# CMUcam_Bridge.net
KiCad netlist of a schematic drawn in EAGLE
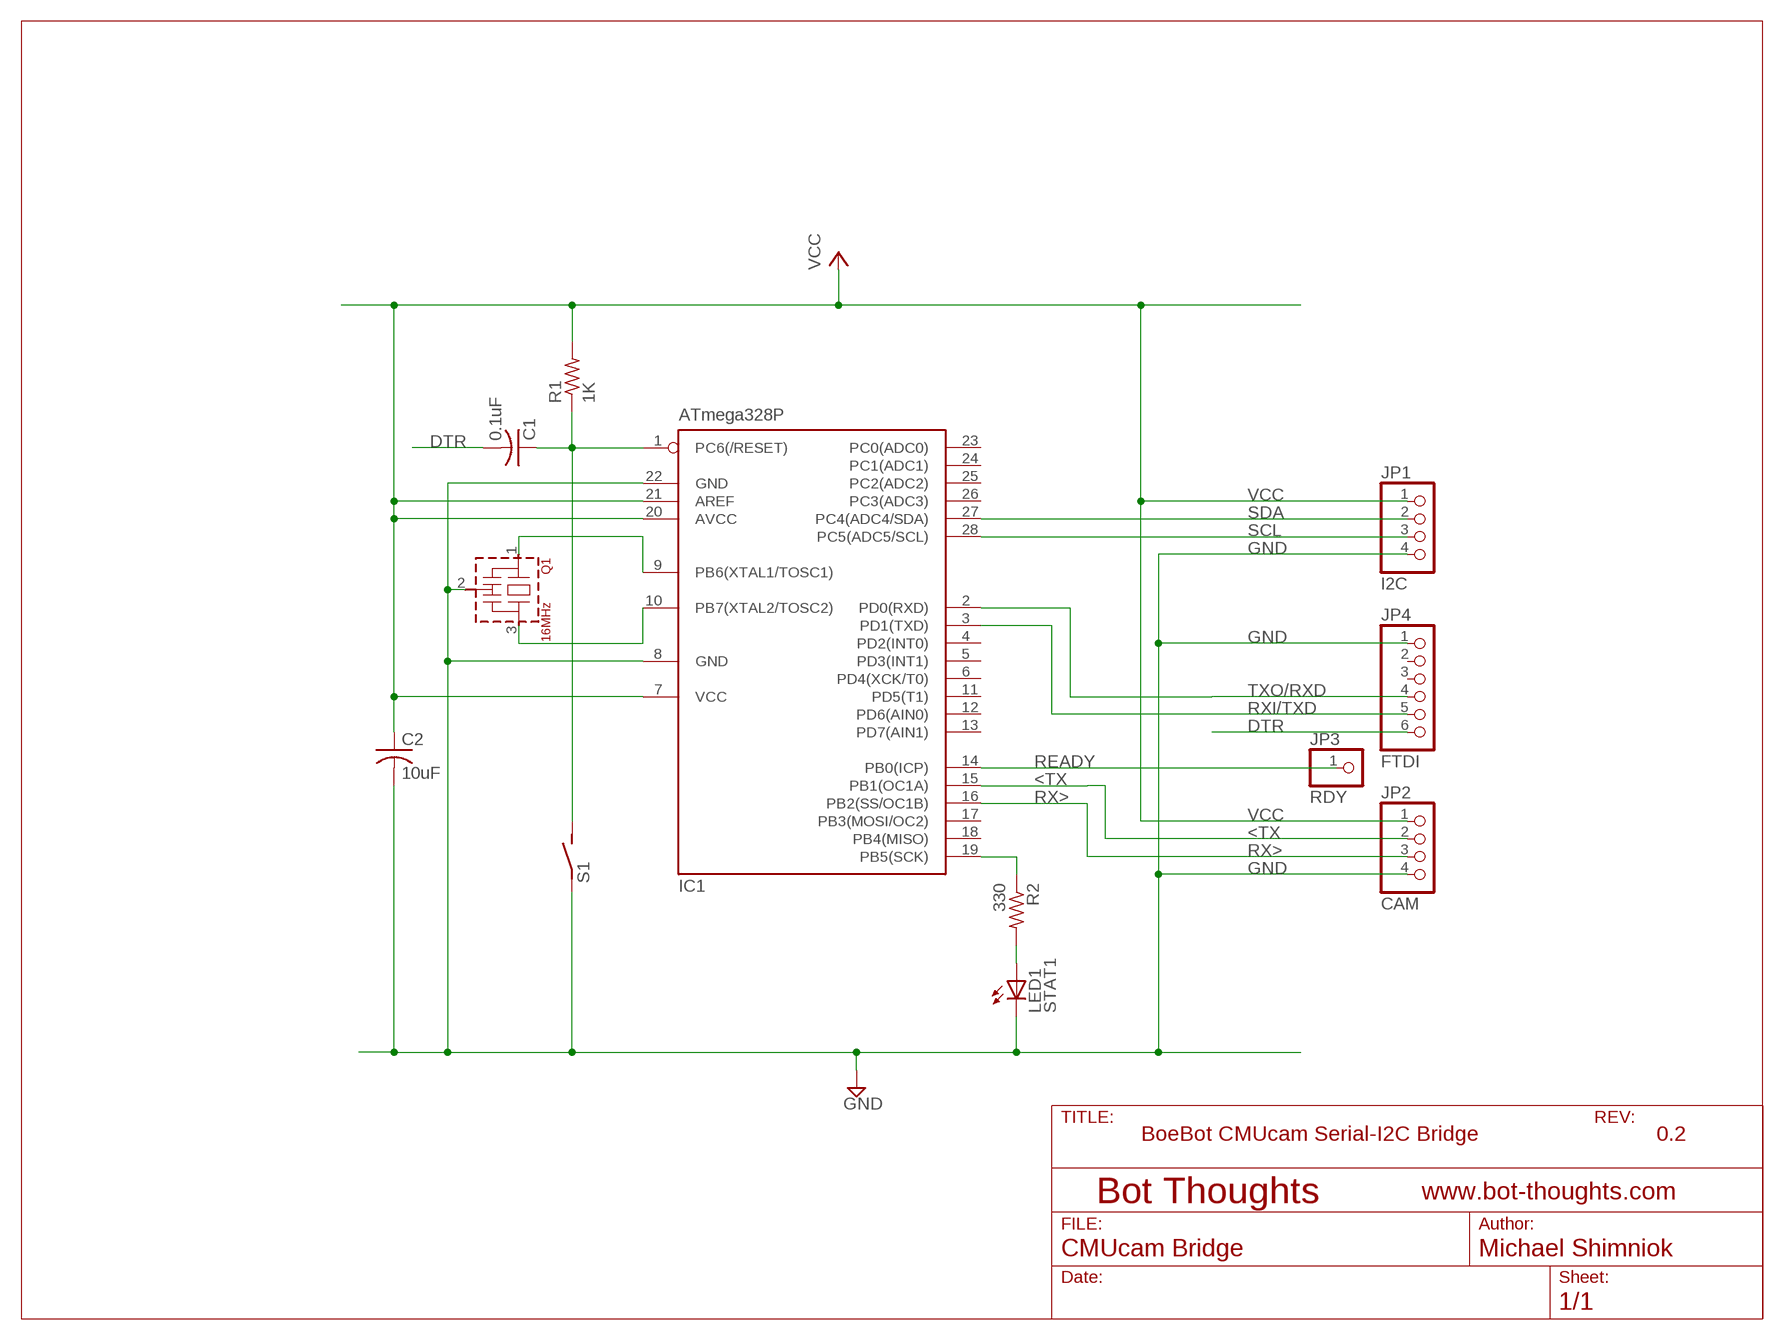
[diagram p0: schematic, sheet 1]

(export (version "E")
  (design (tool "Eeschema 10.0.6"))
  (components
    (comp (ref "C1")
      (value "0.1uF")
      (footprint "eagle-import:C0603")
      (fields (field (name "PARTNO") "CC0603ZRY5V7BB104"))
      (libsource (lib "eagle-import") (part "C-USC0603"))
    )
    (comp (ref "C2")
      (value "10uF")
      (footprint "eagle-import:C0805")
      (fields (field (name "PARTNO") "C1608X5R0J105K"))
      (libsource (lib "eagle-import") (part "C-USC0805"))
    )
    (comp (ref "IC1")
      (value "ATmega328P")
      (footprint "eagle-import:DIL28-3")
      (fields (field (name "PARTNO") "DEV-10524"))
      (libsource (lib "eagle-import") (part "MEGA8-P"))
    )
    (comp (ref "JP1")
      (value "I2C")
      (footprint "eagle-import:1X04-S")
      (fields (field (name "PARTNO") "2211S-04G"))
      (libsource (lib "eagle-import") (part "PINHD-1X04_2.54-S"))
    )
    (comp (ref "JP2")
      (value "CAM")
      (footprint "eagle-import:1X04-S")
      (fields (field (name "PARTNO") "2211S-04G"))
      (libsource (lib "eagle-import") (part "PINHD-1X04_2.54-S"))
    )
    (comp (ref "JP3")
      (value "RDY")
      (footprint "eagle-import:1X01-S")
      (libsource (lib "eagle-import") (part "PINHD-1X01_2.54-S"))
    )
    (comp (ref "JP4")
      (value "FTDI")
      (footprint "eagle-import:1X06-S")
      (fields (field (name "PARTNO") "2211S-06G"))
      (libsource (lib "eagle-import") (part "PINHD-1X06_2.54-S"))
    )
    (comp (ref "LED1")
      (value "STAT1")
      (footprint "eagle-import:LED3MM")
      (libsource (lib "eagle-import") (part "LED3MM"))
    )
    (comp (ref "Q1")
      (value "16MHz")
      (footprint "eagle-import:CSTLS_G9")
      (fields (field (name "PARTNO") "AWCR-16.00MD"))
      (libsource (lib "eagle-import") (part "murata-resonators_CSTLS_G"))
    )
    (comp (ref "R1")
      (value "1K")
      (footprint "eagle-import:0204_7")
      (libsource (lib "eagle-import") (part "R-US_0204/7"))
    )
    (comp (ref "R2")
      (value "330")
      (footprint "eagle-import:R0603")
      (fields (field (name "PARTNO") "CRCW0603330RJNEA"))
      (libsource (lib "eagle-import") (part "R-US_R0603"))
    )
    (comp (ref "S1")
      (value "RESET\\")
      (footprint "eagle-import:EVQ11X09")
      (fields (field (name "PARTNO") "SALVAGE"))
      (libsource (lib "eagle-import") (part "SPST2EVQ11X09"))
    )
  )
  (nets
    (net (code "1") (name "/<TX") (class "Default")
      (node (ref "IC1") (pin "15") (pinfunction "PB1(OC1A)_15") (pintype "bidirectional"))
      (node (ref "JP2") (pin "2") (pinfunction "2_2") (pintype "passive"))
    )
    (net (code "2") (name "/DTR") (class "Default")
      (node (ref "C1") (pin "2") (pinfunction "2_2") (pintype "passive"))
      (node (ref "JP4") (pin "6") (pinfunction "6_6") (pintype "passive"))
    )
    (net (code "3") (name "/READY") (class "Default")
      (node (ref "IC1") (pin "14") (pinfunction "PB0(ICP)_14") (pintype "bidirectional"))
      (node (ref "JP3") (pin "1") (pinfunction "1_1") (pintype "passive"))
    )
    (net (code "4") (name "/RX>") (class "Default")
      (node (ref "IC1") (pin "16") (pinfunction "PB2(SS/OC1B)_16") (pintype "bidirectional"))
      (node (ref "JP2") (pin "3") (pinfunction "3_3") (pintype "passive"))
    )
    (net (code "5") (name "/RXI{slash}TXD") (class "Default")
      (node (ref "IC1") (pin "3") (pinfunction "PD1(TXD)_3") (pintype "bidirectional"))
      (node (ref "JP4") (pin "5") (pinfunction "5_5") (pintype "passive"))
    )
    (net (code "6") (name "/SCL") (class "Default")
      (node (ref "IC1") (pin "28") (pinfunction "PC5(ADC5/SCL)_28") (pintype "bidirectional"))
      (node (ref "JP1") (pin "3") (pinfunction "3_3") (pintype "passive"))
    )
    (net (code "7") (name "/SDA") (class "Default")
      (node (ref "IC1") (pin "27") (pinfunction "PC4(ADC4/SDA)_27") (pintype "bidirectional"))
      (node (ref "JP1") (pin "2") (pinfunction "2_2") (pintype "passive"))
    )
    (net (code "8") (name "/TXO{slash}RXD") (class "Default")
      (node (ref "IC1") (pin "2") (pinfunction "PD0(RXD)_2") (pintype "bidirectional"))
      (node (ref "JP4") (pin "4") (pinfunction "4_4") (pintype "passive"))
    )
    (net (code "9") (name "GND") (class "Default")
      (node (ref "C2") (pin "2") (pinfunction "2_2") (pintype "passive"))
      (node (ref "IC1") (pin "22") (pinfunction "GND_22") (pintype "power_in"))
      (node (ref "IC1") (pin "8") (pinfunction "GND_8") (pintype "power_in"))
      (node (ref "JP1") (pin "4") (pinfunction "4_4") (pintype "passive"))
      (node (ref "JP2") (pin "4") (pinfunction "4_4") (pintype "passive"))
      (node (ref "JP4") (pin "1") (pinfunction "1_1") (pintype "passive"))
      (node (ref "LED1") (pin "K") (pinfunction "C_K") (pintype "passive"))
      (node (ref "Q1") (pin "2") (pinfunction "VSS_2") (pintype "power_in"))
      (node (ref "S1") (pin "1") (pinfunction "1_1") (pintype "passive"))
    )
    (net (code "10") (name "Net-(IC1-PB5(SCK))") (class "Default")
      (node (ref "IC1") (pin "19") (pinfunction "PB5(SCK)_19") (pintype "bidirectional"))
      (node (ref "R2") (pin "1") (pinfunction "1_1") (pintype "passive"))
    )
    (net (code "11") (name "Net-(IC1-PB6(XTAL1{slash}TOSC1))") (class "Default")
      (node (ref "IC1") (pin "9") (pinfunction "PB6(XTAL1/TOSC1)_9") (pintype "bidirectional"))
      (node (ref "Q1") (pin "1") (pinfunction "1_1") (pintype "output"))
    )
    (net (code "12") (name "Net-(IC1-PB7(XTAL2{slash}TOSC2))") (class "Default")
      (node (ref "IC1") (pin "10") (pinfunction "PB7(XTAL2/TOSC2)_10") (pintype "bidirectional"))
      (node (ref "Q1") (pin "3") (pinfunction "3_3") (pintype "input"))
    )
    (net (code "13") (name "Net-(IC1-PC6({slash}RESET))") (class "Default")
      (node (ref "C1") (pin "1") (pinfunction "1_1") (pintype "passive"))
      (node (ref "IC1") (pin "1") (pinfunction "PC6(/RESET)_1") (pintype "bidirectional"))
      (node (ref "R1") (pin "1") (pinfunction "1_1") (pintype "passive"))
      (node (ref "S1") (pin "2") (pinfunction "2_2") (pintype "passive"))
    )
    (net (code "14") (name "Net-(LED1-PadA)") (class "Default")
      (node (ref "LED1") (pin "A") (pinfunction "A_A") (pintype "passive"))
      (node (ref "R2") (pin "2") (pinfunction "2_2") (pintype "passive"))
    )
    (net (code "15") (name "VCC") (class "Default")
      (node (ref "C2") (pin "1") (pinfunction "1_1") (pintype "passive"))
      (node (ref "IC1") (pin "20") (pinfunction "AVCC_20") (pintype "power_in"))
      (node (ref "IC1") (pin "21") (pinfunction "AREF_21") (pintype "passive"))
      (node (ref "IC1") (pin "7") (pinfunction "VCC_7") (pintype "power_in"))
      (node (ref "JP1") (pin "1") (pinfunction "1_1") (pintype "passive"))
      (node (ref "JP2") (pin "1") (pinfunction "1_1") (pintype "passive"))
      (node (ref "R1") (pin "2") (pinfunction "2_2") (pintype "passive"))
    )
    (net (code "16") (name "unconnected-(IC1-PB3(MOSI{slash}OC2)-Pad17)") (class "Default")
      (node (ref "IC1") (pin "17") (pinfunction "PB3(MOSI/OC2)_17") (pintype "bidirectional"))
    )
    (net (code "17") (name "unconnected-(IC1-PB4(MISO)-Pad18)") (class "Default")
      (node (ref "IC1") (pin "18") (pinfunction "PB4(MISO)_18") (pintype "bidirectional"))
    )
    (net (code "18") (name "unconnected-(IC1-PC0(ADC0)-Pad23)") (class "Default")
      (node (ref "IC1") (pin "23") (pinfunction "PC0(ADC0)_23") (pintype "bidirectional"))
    )
    (net (code "19") (name "unconnected-(IC1-PC1(ADC1)-Pad24)") (class "Default")
      (node (ref "IC1") (pin "24") (pinfunction "PC1(ADC1)_24") (pintype "bidirectional"))
    )
    (net (code "20") (name "unconnected-(IC1-PC2(ADC2)-Pad25)") (class "Default")
      (node (ref "IC1") (pin "25") (pinfunction "PC2(ADC2)_25") (pintype "bidirectional"))
    )
    (net (code "21") (name "unconnected-(IC1-PC3(ADC3)-Pad26)") (class "Default")
      (node (ref "IC1") (pin "26") (pinfunction "PC3(ADC3)_26") (pintype "bidirectional"))
    )
    (net (code "22") (name "unconnected-(IC1-PD2(INT0)-Pad4)") (class "Default")
      (node (ref "IC1") (pin "4") (pinfunction "PD2(INT0)_4") (pintype "bidirectional"))
    )
    (net (code "23") (name "unconnected-(IC1-PD3(INT1)-Pad5)") (class "Default")
      (node (ref "IC1") (pin "5") (pinfunction "PD3(INT1)_5") (pintype "bidirectional"))
    )
    (net (code "24") (name "unconnected-(IC1-PD4(XCK{slash}T0)-Pad6)") (class "Default")
      (node (ref "IC1") (pin "6") (pinfunction "PD4(XCK/T0)_6") (pintype "bidirectional"))
    )
    (net (code "25") (name "unconnected-(IC1-PD5(T1)-Pad11)") (class "Default")
      (node (ref "IC1") (pin "11") (pinfunction "PD5(T1)_11") (pintype "bidirectional"))
    )
    (net (code "26") (name "unconnected-(IC1-PD6(AIN0)-Pad12)") (class "Default")
      (node (ref "IC1") (pin "12") (pinfunction "PD6(AIN0)_12") (pintype "bidirectional"))
    )
    (net (code "27") (name "unconnected-(IC1-PD7(AIN1)-Pad13)") (class "Default")
      (node (ref "IC1") (pin "13") (pinfunction "PD7(AIN1)_13") (pintype "bidirectional"))
    )
    (net (code "28") (name "unconnected-(JP4-Pad2)") (class "Default")
      (node (ref "JP4") (pin "2") (pinfunction "2_2") (pintype "passive"))
    )
    (net (code "29") (name "unconnected-(JP4-Pad3)") (class "Default")
      (node (ref "JP4") (pin "3") (pinfunction "3_3") (pintype "passive"))
    )
  )
)
